# co2-sensor.net
KiCad netlist of a schematic drawn in EAGLE
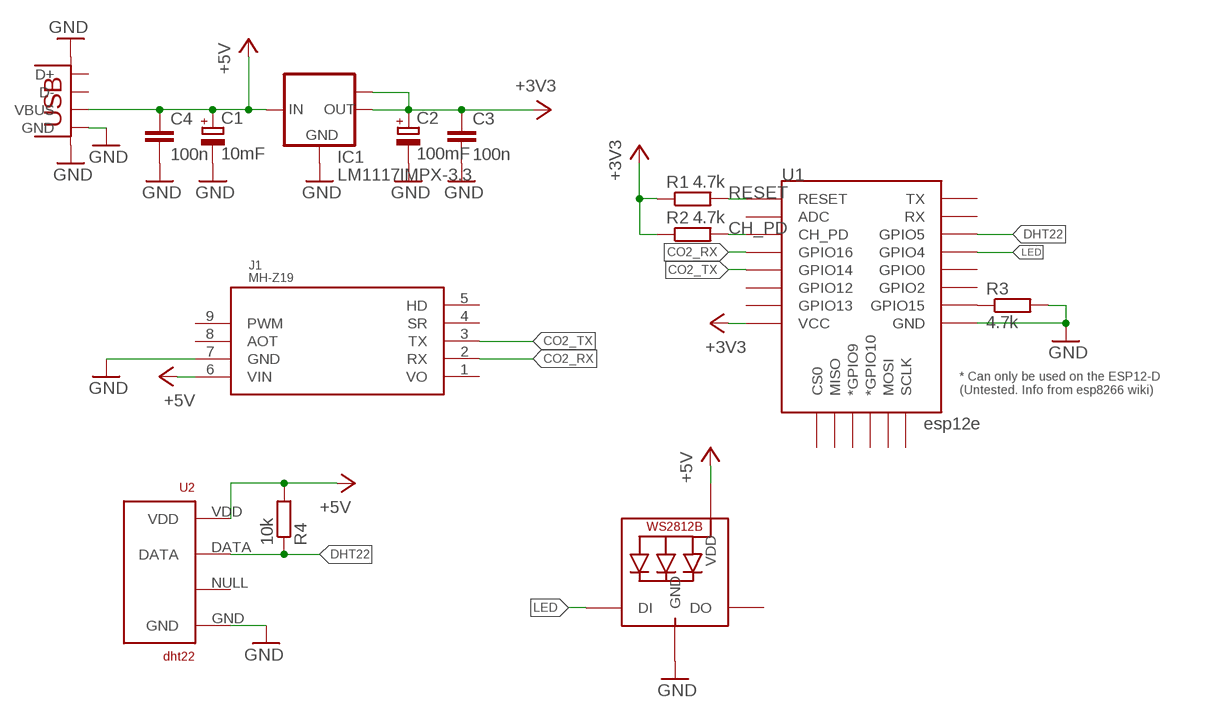
[diagram p0: schematic, sheet 1]

(export (version "E")
  (design (tool "Eeschema 10.0.6"))
  (components
    (comp (ref "C1")
      (value "10mF")
      (footprint "eagle-import:CT3216")
      (libsource (lib "eagle-import") (part "CPOL-EUCT3216"))
    )
    (comp (ref "C2")
      (value "100mF")
      (footprint "eagle-import:CT3216")
      (libsource (lib "eagle-import") (part "CPOL-EUCT3216"))
    )
    (comp (ref "C3")
      (value "100n")
      (footprint "eagle-import:C0805")
      (libsource (lib "eagle-import") (part "C-EUC0805"))
    )
    (comp (ref "C4")
      (value "100n")
      (footprint "eagle-import:C0805")
      (libsource (lib "eagle-import") (part "C-EUC0805"))
    )
    (comp (ref "IC1")
      (value "LM1117IMPX-3.3")
      (footprint "eagle-import:SOT223")
      (libsource (lib "eagle-import") (part "LM1117IMPX-3.3"))
    )
    (comp (ref "J1")
      (value "MH-Z19")
      (footprint "eagle-import:MH-Z19-REV")
      (libsource (lib "eagle-import") (part "MH-Z19"))
    )
    (comp (ref "LED1")
      (value "WS2812B_5050N")
      (footprint "eagle-import:WS2812B-NARROW")
      (fields (field (name "MF") "Worldsemi") (field (name "MP") "WS2812B"))
      (libsource (lib "eagle-import") (part "WS2812B_5050N"))
    )
    (comp (ref "R1")
      (value "4.7k")
      (footprint "eagle-import:M0805")
      (libsource (lib "eagle-import") (part "R-EU_M0805"))
    )
    (comp (ref "R2")
      (value "4.7k")
      (footprint "eagle-import:M0805")
      (libsource (lib "eagle-import") (part "R-EU_M0805"))
    )
    (comp (ref "R3")
      (value "4.7k")
      (footprint "eagle-import:M0805")
      (libsource (lib "eagle-import") (part "R-EU_M0805"))
    )
    (comp (ref "R4")
      (value "10k")
      (footprint "eagle-import:M0805")
      (libsource (lib "eagle-import") (part "R-EU_M0805"))
    )
    (comp (ref "U$1")
      (value "USB-A")
      (footprint "eagle-import:USB-A-SMT")
      (libsource (lib "eagle-import") (part "USB-A"))
    )
    (comp (ref "U1")
      (value "esp12e")
      (footprint "eagle-import:ESP12E-SMD")
      (libsource (lib "eagle-import") (part "ESP12ESMD"))
    )
    (comp (ref "U2")
      (value "dht22")
      (footprint "eagle-import:AM2302")
      (libsource (lib "eagle-import") (part "RHT03_DHT-22_AM2302WIRED"))
    )
  )
  (nets
    (net (code "1") (name "+3V3") (class "Default")
      (node (ref "C2") (pin "+") (pinfunction "+_+") (pintype "passive"))
      (node (ref "C3") (pin "1") (pinfunction "1_1") (pintype "passive"))
      (node (ref "IC1") (pin "2") (pinfunction "OUT_2") (pintype "passive"))
      (node (ref "IC1") (pin "TAB") (pinfunction "OUT1_TAB") (pintype "passive"))
      (node (ref "R1") (pin "1") (pinfunction "1_1") (pintype "passive"))
      (node (ref "R2") (pin "1") (pinfunction "1_1") (pintype "passive"))
      (node (ref "U1") (pin "VCC") (pinfunction "VCC_VCC") (pintype "bidirectional"))
    )
    (net (code "2") (name "+5V") (class "Default")
      (node (ref "C1") (pin "+") (pinfunction "+_+") (pintype "passive"))
      (node (ref "C4") (pin "1") (pinfunction "1_1") (pintype "passive"))
      (node (ref "IC1") (pin "3") (pinfunction "IN_3") (pintype "input"))
      (node (ref "J1") (pin "6") (pinfunction "VIN_6") (pintype "power_in"))
      (node (ref "LED1") (pin "1-VDD") (pinfunction "VDD_1-VDD") (pintype "power_in"))
      (node (ref "R4") (pin "2") (pinfunction "2_2") (pintype "passive"))
      (node (ref "U$1") (pin "P$6") (pinfunction "VBUS_P$6") (pintype "power_in"))
      (node (ref "U2") (pin "VDD") (pinfunction "VDD_VDD") (pintype "power_in"))
    )
    (net (code "3") (name "/CH_PD") (class "Default")
      (node (ref "R2") (pin "2") (pinfunction "2_2") (pintype "passive"))
      (node (ref "U1") (pin "CH_PD") (pinfunction "CH_PD_CH_PD") (pintype "bidirectional"))
    )
    (net (code "4") (name "/RESET") (class "Default")
      (node (ref "R1") (pin "2") (pinfunction "2_2") (pintype "passive"))
      (node (ref "U1") (pin "RESET") (pinfunction "RESET_RESET") (pintype "bidirectional"))
    )
    (net (code "5") (name "/VO") (class "Default")
      (node (ref "J1") (pin "1") (pinfunction "VO_1") (pintype "power_in"))
    )
    (net (code "6") (name "CO2_RX") (class "Default")
      (node (ref "J1") (pin "2") (pinfunction "RX_2") (pintype "input"))
      (node (ref "U1") (pin "GPIO16") (pinfunction "GPIO16_GPIO16") (pintype "bidirectional"))
    )
    (net (code "7") (name "CO2_TX") (class "Default")
      (node (ref "J1") (pin "3") (pinfunction "TX_3") (pintype "output"))
      (node (ref "U1") (pin "GPIO14") (pinfunction "GPIO14_GPIO14") (pintype "bidirectional"))
    )
    (net (code "8") (name "DHT22") (class "Default")
      (node (ref "R4") (pin "1") (pinfunction "1_1") (pintype "passive"))
      (node (ref "U1") (pin "GPIO5") (pinfunction "GPIO5_GPIO5") (pintype "bidirectional"))
      (node (ref "U2") (pin "DATA") (pinfunction "DATA_DATA") (pintype "bidirectional"))
    )
    (net (code "9") (name "GND") (class "Default")
      (node (ref "C1") (pin "-") (pinfunction "-_-") (pintype "passive"))
      (node (ref "C2") (pin "-") (pinfunction "-_-") (pintype "passive"))
      (node (ref "C3") (pin "2") (pinfunction "2_2") (pintype "passive"))
      (node (ref "C4") (pin "2") (pinfunction "2_2") (pintype "passive"))
      (node (ref "IC1") (pin "1") (pinfunction "GND_1") (pintype "input"))
      (node (ref "J1") (pin "7") (pinfunction "GND_7") (pintype "power_in"))
      (node (ref "LED1") (pin "3-GND") (pinfunction "GND_3-GND") (pintype "power_in"))
      (node (ref "R3") (pin "2") (pinfunction "2_2") (pintype "passive"))
      (node (ref "U$1") (pin "P$1") (pinfunction "GND_P$1") (pintype "power_in"))
      (node (ref "U$1") (pin "P$2") (pinfunction "GND_P$2") (pintype "power_in"))
      (node (ref "U$1") (pin "P$3") (pinfunction "GND_P$3") (pintype "power_in"))
      (node (ref "U1") (pin "GND") (pinfunction "GND_GND") (pintype "bidirectional"))
      (node (ref "U2") (pin "GND") (pinfunction "GND_GND") (pintype "power_in"))
    )
    (net (code "10") (name "LED") (class "Default")
      (node (ref "LED1") (pin "4-DIN") (pinfunction "DI_4-DIN") (pintype "input"))
      (node (ref "U1") (pin "GPIO4") (pinfunction "GPIO4_GPIO4") (pintype "bidirectional"))
    )
    (net (code "11") (name "Net-(R3-Pad1)") (class "Default")
      (node (ref "R3") (pin "1") (pinfunction "1_1") (pintype "passive"))
      (node (ref "U1") (pin "GPIO15") (pinfunction "GPIO15_GPIO15") (pintype "bidirectional"))
    )
    (net (code "12") (name "unconnected-(J1-AOT-Pad8)") (class "Default")
      (node (ref "J1") (pin "8") (pinfunction "AOT_8") (pintype "no_connect"))
    )
    (net (code "13") (name "unconnected-(J1-HD-Pad5)") (class "Default")
      (node (ref "J1") (pin "5") (pinfunction "HD_5") (pintype "input"))
    )
    (net (code "14") (name "unconnected-(J1-PWM-Pad9)") (class "Default")
      (node (ref "J1") (pin "9") (pinfunction "PWM_9") (pintype "output"))
    )
    (net (code "15") (name "unconnected-(J1-SR-Pad4)") (class "Default")
      (node (ref "J1") (pin "4") (pinfunction "SR_4") (pintype "no_connect"))
    )
    (net (code "16") (name "unconnected-(LED1-DO-Pad2-DOUT)") (class "Default")
      (node (ref "LED1") (pin "2-DOUT") (pinfunction "DO_2-DOUT") (pintype "output"))
    )
    (net (code "17") (name "unconnected-(U$1-D+-PadP$4)") (class "Default")
      (node (ref "U$1") (pin "P$4") (pinfunction "D+_P$4") (pintype "bidirectional"))
    )
    (net (code "18") (name "unconnected-(U$1-D--PadP$5)") (class "Default")
      (node (ref "U$1") (pin "P$5") (pinfunction "D-_P$5") (pintype "bidirectional"))
    )
    (net (code "19") (name "unconnected-(U1-*GPIO9-PadGPIO9)") (class "Default")
      (node (ref "U1") (pin "GPIO9") (pinfunction "*GPIO9_GPIO9") (pintype "bidirectional"))
    )
    (net (code "20") (name "unconnected-(U1-*GPIO10-PadGPIO10)") (class "Default")
      (node (ref "U1") (pin "GPIO10") (pinfunction "*GPIO10_GPIO10") (pintype "bidirectional"))
    )
    (net (code "21") (name "unconnected-(U1-PadADC)") (class "Default")
      (node (ref "U1") (pin "ADC") (pinfunction "ADC_ADC") (pintype "bidirectional"))
    )
    (net (code "22") (name "unconnected-(U1-PadCS0)") (class "Default")
      (node (ref "U1") (pin "CS0") (pinfunction "CS0_CS0") (pintype "bidirectional"))
    )
    (net (code "23") (name "unconnected-(U1-PadGPIO0)") (class "Default")
      (node (ref "U1") (pin "GPIO0") (pinfunction "GPIO0_GPIO0") (pintype "bidirectional"))
    )
    (net (code "24") (name "unconnected-(U1-PadGPIO2)") (class "Default")
      (node (ref "U1") (pin "GPIO2") (pinfunction "GPIO2_GPIO2") (pintype "bidirectional"))
    )
    (net (code "25") (name "unconnected-(U1-PadGPIO12)") (class "Default")
      (node (ref "U1") (pin "GPIO12") (pinfunction "GPIO12_GPIO12") (pintype "bidirectional"))
    )
    (net (code "26") (name "unconnected-(U1-PadGPIO13)") (class "Default")
      (node (ref "U1") (pin "GPIO13") (pinfunction "GPIO13_GPIO13") (pintype "bidirectional"))
    )
    (net (code "27") (name "unconnected-(U1-PadMISO)") (class "Default")
      (node (ref "U1") (pin "MISO") (pinfunction "MISO_MISO") (pintype "bidirectional"))
    )
    (net (code "28") (name "unconnected-(U1-PadMOSI)") (class "Default")
      (node (ref "U1") (pin "MOSI") (pinfunction "MOSI_MOSI") (pintype "bidirectional"))
    )
    (net (code "29") (name "unconnected-(U1-PadSCLK)") (class "Default")
      (node (ref "U1") (pin "SCLK") (pinfunction "SCLK_SCLK") (pintype "bidirectional"))
    )
    (net (code "30") (name "unconnected-(U1-RX-PadRXD0)") (class "Default")
      (node (ref "U1") (pin "RXD0") (pinfunction "RX_RXD0") (pintype "bidirectional"))
    )
    (net (code "31") (name "unconnected-(U1-TX-PadTXD0)") (class "Default")
      (node (ref "U1") (pin "TXD0") (pinfunction "TX_TXD0") (pintype "bidirectional"))
    )
    (net (code "32") (name "unconnected-(U2-PadNULL)") (class "Default")
      (node (ref "U2") (pin "NULL") (pinfunction "NULL_NULL") (pintype "no_connect"))
    )
  )
)
